# Adafruit_USB_Isolator.net
KiCad netlist of a schematic drawn in EAGLE
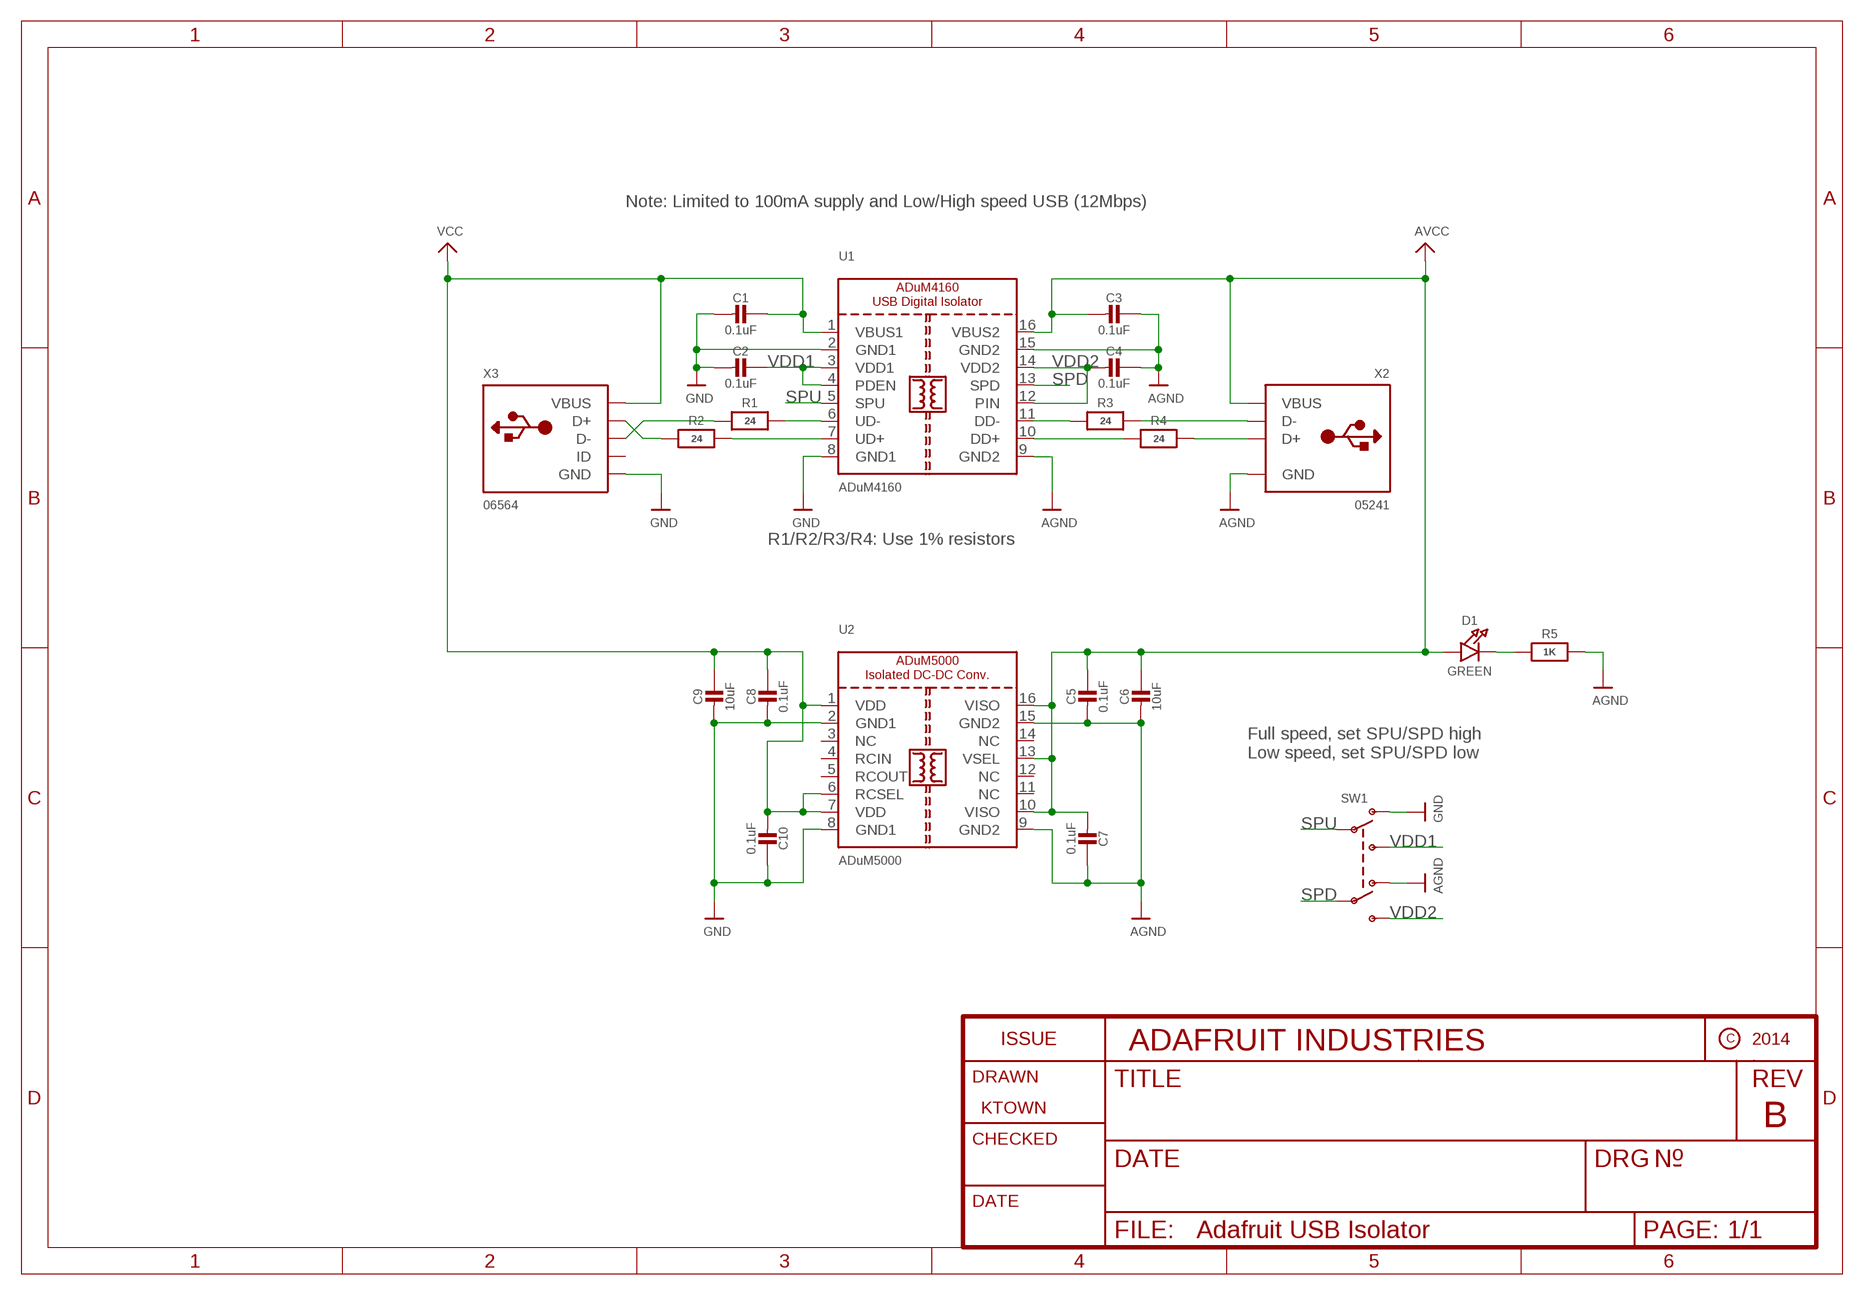
[diagram p0: schematic, sheet 1]

(export (version "E")
  (design (tool "Eeschema 10.0.6"))
  (components
    (comp (ref "C1")
      (value "0.1uF")
      (footprint "eagle-import:0805-NO")
      (libsource (lib "eagle-import") (part "CAP_CERAMIC0805-NOOUTLINE"))
    )
    (comp (ref "C2")
      (value "0.1uF")
      (footprint "eagle-import:0805-NO")
      (libsource (lib "eagle-import") (part "CAP_CERAMIC0805-NOOUTLINE"))
    )
    (comp (ref "C3")
      (value "0.1uF")
      (footprint "eagle-import:0805-NO")
      (libsource (lib "eagle-import") (part "CAP_CERAMIC0805-NOOUTLINE"))
    )
    (comp (ref "C4")
      (value "0.1uF")
      (footprint "eagle-import:0805-NO")
      (libsource (lib "eagle-import") (part "CAP_CERAMIC0805-NOOUTLINE"))
    )
    (comp (ref "C5")
      (value "0.1uF")
      (footprint "eagle-import:0805-NO")
      (libsource (lib "eagle-import") (part "CAP_CERAMIC0805-NOOUTLINE"))
    )
    (comp (ref "C6")
      (value "10uF")
      (footprint "eagle-import:0805-NO")
      (libsource (lib "eagle-import") (part "CAP_CERAMIC0805-NOOUTLINE"))
    )
    (comp (ref "C7")
      (value "0.1uF")
      (footprint "eagle-import:0805-NO")
      (libsource (lib "eagle-import") (part "CAP_CERAMIC0805-NOOUTLINE"))
    )
    (comp (ref "C8")
      (value "0.1uF")
      (footprint "eagle-import:0805-NO")
      (libsource (lib "eagle-import") (part "CAP_CERAMIC0805-NOOUTLINE"))
    )
    (comp (ref "C9")
      (value "10uF")
      (footprint "eagle-import:0805-NO")
      (libsource (lib "eagle-import") (part "CAP_CERAMIC0805-NOOUTLINE"))
    )
    (comp (ref "C10")
      (value "0.1uF")
      (footprint "eagle-import:0805-NO")
      (libsource (lib "eagle-import") (part "CAP_CERAMIC0805-NOOUTLINE"))
    )
    (comp (ref "D1")
      (value "GREEN")
      (footprint "eagle-import:CHIPLED_0805_NOOUTLINE")
      (libsource (lib "eagle-import") (part "LED0805_NOOUTLINE"))
    )
    (comp (ref "R1")
      (value "24")
      (footprint "eagle-import:0805-NO")
      (libsource (lib "eagle-import") (part "RESISTOR0805_NOOUTLINE"))
    )
    (comp (ref "R2")
      (value "24")
      (footprint "eagle-import:0805-NO")
      (libsource (lib "eagle-import") (part "RESISTOR0805_NOOUTLINE"))
    )
    (comp (ref "R3")
      (value "24")
      (footprint "eagle-import:0805-NO")
      (libsource (lib "eagle-import") (part "RESISTOR0805_NOOUTLINE"))
    )
    (comp (ref "R4")
      (value "24")
      (footprint "eagle-import:_0805MP")
      (libsource (lib "eagle-import") (part "RESISTOR_0805MP"))
    )
    (comp (ref "R5")
      (value "1K")
      (footprint "eagle-import:0805-NO")
      (libsource (lib "eagle-import") (part "RESISTOR0805_NOOUTLINE"))
    )
    (comp (ref "SW1")
      (value "SWITCH_DPDTEG1390")
      (footprint "eagle-import:EG1390")
      (libsource (lib "eagle-import") (part "SWITCH_DPDTEG1390"))
    )
    (comp (ref "U1")
      (value "ADuM4160")
      (footprint "eagle-import:SOIC16WIDE")
      (libsource (lib "eagle-import") (part "ADUM4160"))
    )
    (comp (ref "U2")
      (value "ADuM5000")
      (footprint "eagle-import:SOIC16WIDE")
      (libsource (lib "eagle-import") (part "ADUM5000"))
    )
    (comp (ref "X2")
      (value "05241")
      (footprint "eagle-import:USB_HOST-PTH")
      (libsource (lib "eagle-import") (part "USB_TYPEAPTHFML"))
    )
    (comp (ref "X3")
      (value "06564")
      (footprint "eagle-import:USB-MINIB_LARGER")
      (libsource (lib "eagle-import") (part "USBMINIBLARGE"))
    )
  )
  (nets
    (net (code "1") (name "/SPD") (class "Default")
      (node (ref "SW1") (pin "P2") (pinfunction "P2_P2") (pintype "passive"))
      (node (ref "U1") (pin "13") (pinfunction "SPD_13") (pintype "input"))
    )
    (net (code "2") (name "/SPU") (class "Default")
      (node (ref "SW1") (pin "P1") (pinfunction "P1_P1") (pintype "passive"))
      (node (ref "U1") (pin "5") (pinfunction "SPU_5") (pintype "input"))
    )
    (net (code "3") (name "/VDD1") (class "Default")
      (node (ref "C2") (pin "1") (pinfunction "1_1") (pintype "passive"))
      (node (ref "SW1") (pin "S1") (pinfunction "S1_S1") (pintype "passive"))
      (node (ref "U1") (pin "3") (pinfunction "VDD1_3") (pintype "power_in"))
      (node (ref "U1") (pin "4") (pinfunction "PDEN_4") (pintype "input"))
    )
    (net (code "4") (name "/VDD2") (class "Default")
      (node (ref "C4") (pin "2") (pinfunction "2_2") (pintype "passive"))
      (node (ref "SW1") (pin "S2") (pinfunction "S2_S2") (pintype "passive"))
      (node (ref "U1") (pin "12") (pinfunction "PIN_12") (pintype "input"))
      (node (ref "U1") (pin "14") (pinfunction "VDD2_14") (pintype "power_in"))
    )
    (net (code "5") (name "AGND") (class "Default")
      (node (ref "C3") (pin "1") (pinfunction "1_1") (pintype "passive"))
      (node (ref "C4") (pin "1") (pinfunction "1_1") (pintype "passive"))
      (node (ref "C5") (pin "2") (pinfunction "2_2") (pintype "passive"))
      (node (ref "C6") (pin "2") (pinfunction "2_2") (pintype "passive"))
      (node (ref "C7") (pin "1") (pinfunction "1_1") (pintype "passive"))
      (node (ref "R5") (pin "2") (pinfunction "2_2") (pintype "passive"))
      (node (ref "SW1") (pin "O2") (pinfunction "O2_O2") (pintype "passive"))
      (node (ref "U1") (pin "15") (pinfunction "GND2_15") (pintype "power_in"))
      (node (ref "U1") (pin "9") (pinfunction "GND2_9") (pintype "power_in"))
      (node (ref "U2") (pin "15") (pinfunction "GND2_15") (pintype "power_in"))
      (node (ref "U2") (pin "9") (pinfunction "GND2_9") (pintype "power_in"))
      (node (ref "X2") (pin "GND") (pinfunction "GND_GND") (pintype "power_in"))
    )
    (net (code "6") (name "AVCC") (class "Default")
      (node (ref "C3") (pin "2") (pinfunction "2_2") (pintype "passive"))
      (node (ref "C5") (pin "1") (pinfunction "1_1") (pintype "passive"))
      (node (ref "C6") (pin "1") (pinfunction "1_1") (pintype "passive"))
      (node (ref "C7") (pin "2") (pinfunction "2_2") (pintype "passive"))
      (node (ref "D1") (pin "A") (pinfunction "A_A") (pintype "passive"))
      (node (ref "U1") (pin "16") (pinfunction "VBUS2_16") (pintype "power_in"))
      (node (ref "U2") (pin "10") (pinfunction "VISO_10") (pintype "bidirectional"))
      (node (ref "U2") (pin "13") (pinfunction "VSEL_13") (pintype "input"))
      (node (ref "U2") (pin "16") (pinfunction "VISO_16") (pintype "power_in"))
      (node (ref "X2") (pin "VBUS") (pinfunction "VBUS_VBUS") (pintype "power_in"))
    )
    (net (code "7") (name "GND") (class "Default")
      (node (ref "C1") (pin "2") (pinfunction "2_2") (pintype "passive"))
      (node (ref "C10") (pin "1") (pinfunction "1_1") (pintype "passive"))
      (node (ref "C2") (pin "2") (pinfunction "2_2") (pintype "passive"))
      (node (ref "C8") (pin "2") (pinfunction "2_2") (pintype "passive"))
      (node (ref "C9") (pin "2") (pinfunction "2_2") (pintype "passive"))
      (node (ref "SW1") (pin "O1") (pinfunction "O1_O1") (pintype "passive"))
      (node (ref "U1") (pin "2") (pinfunction "GND1_2") (pintype "power_in"))
      (node (ref "U1") (pin "8") (pinfunction "GND1_8") (pintype "power_in"))
      (node (ref "U2") (pin "2") (pinfunction "GND1_2") (pintype "power_in"))
      (node (ref "U2") (pin "8") (pinfunction "GND1_8") (pintype "power_in"))
      (node (ref "X3") (pin "GND") (pinfunction "GND_GND") (pintype "power_in"))
      (node (ref "X3") (pin "GND1") (pinfunction "GND_GND1") (pintype "power_in"))
      (node (ref "X3") (pin "GND2") (pinfunction "GND_GND2") (pintype "power_in"))
      (node (ref "X3") (pin "GND3") (pinfunction "GND_GND3") (pintype "power_in"))
      (node (ref "X3") (pin "GND4") (pinfunction "GND_GND4") (pintype "power_in"))
    )
    (net (code "8") (name "Net-(D1-PadC)") (class "Default")
      (node (ref "D1") (pin "C") (pinfunction "C_C") (pintype "passive"))
      (node (ref "R5") (pin "1") (pinfunction "1_1") (pintype "passive"))
    )
    (net (code "9") (name "Net-(R1-Pad1)") (class "Default")
      (node (ref "R1") (pin "1") (pinfunction "1_1") (pintype "passive"))
      (node (ref "X3") (pin "D-") (pinfunction "D-_D-") (pintype "bidirectional"))
    )
    (net (code "10") (name "Net-(R2-Pad1)") (class "Default")
      (node (ref "R2") (pin "1") (pinfunction "1_1") (pintype "passive"))
      (node (ref "X3") (pin "D+") (pinfunction "D+_D+") (pintype "bidirectional"))
    )
    (net (code "11") (name "Net-(R3-Pad2)") (class "Default")
      (node (ref "R3") (pin "2") (pinfunction "2_2") (pintype "passive"))
      (node (ref "X2") (pin "D-") (pinfunction "D-_D-") (pintype "bidirectional"))
    )
    (net (code "12") (name "Net-(R4-Pad2)") (class "Default")
      (node (ref "R4") (pin "2") (pinfunction "2_2") (pintype "passive"))
      (node (ref "X2") (pin "D+") (pinfunction "D+_D+") (pintype "bidirectional"))
    )
    (net (code "13") (name "Net-(U1-DD+)") (class "Default")
      (node (ref "R4") (pin "1") (pinfunction "1_1") (pintype "passive"))
      (node (ref "U1") (pin "10") (pinfunction "DD+_10") (pintype "bidirectional"))
    )
    (net (code "14") (name "Net-(U1-DD-)") (class "Default")
      (node (ref "R3") (pin "1") (pinfunction "1_1") (pintype "passive"))
      (node (ref "U1") (pin "11") (pinfunction "DD-_11") (pintype "bidirectional"))
    )
    (net (code "15") (name "Net-(U1-UD+)") (class "Default")
      (node (ref "R2") (pin "2") (pinfunction "2_2") (pintype "passive"))
      (node (ref "U1") (pin "7") (pinfunction "UD+_7") (pintype "bidirectional"))
    )
    (net (code "16") (name "Net-(U1-UD-)") (class "Default")
      (node (ref "R1") (pin "2") (pinfunction "2_2") (pintype "passive"))
      (node (ref "U1") (pin "6") (pinfunction "UD-_6") (pintype "bidirectional"))
    )
    (net (code "17") (name "VCC") (class "Default")
      (node (ref "C1") (pin "1") (pinfunction "1_1") (pintype "passive"))
      (node (ref "C10") (pin "2") (pinfunction "2_2") (pintype "passive"))
      (node (ref "C8") (pin "1") (pinfunction "1_1") (pintype "passive"))
      (node (ref "C9") (pin "1") (pinfunction "1_1") (pintype "passive"))
      (node (ref "U1") (pin "1") (pinfunction "VBUS1_1") (pintype "power_in"))
      (node (ref "U2") (pin "1") (pinfunction "VDD_1") (pintype "power_in"))
      (node (ref "U2") (pin "6") (pinfunction "RCSEL_6") (pintype "input"))
      (node (ref "U2") (pin "7") (pinfunction "VDD_7") (pintype "bidirectional"))
      (node (ref "X3") (pin "VBUS") (pinfunction "VBUS_VBUS") (pintype "power_in"))
    )
    (net (code "18") (name "unconnected-(U2-NC-Pad3)") (class "Default")
      (node (ref "U2") (pin "3") (pinfunction "NC_3") (pintype "no_connect"))
    )
    (net (code "19") (name "unconnected-(U2-NC-Pad11)") (class "Default")
      (node (ref "U2") (pin "11") (pinfunction "NC_11") (pintype "no_connect"))
    )
    (net (code "20") (name "unconnected-(U2-NC-Pad12)") (class "Default")
      (node (ref "U2") (pin "12") (pinfunction "NC_12") (pintype "no_connect"))
    )
    (net (code "21") (name "unconnected-(U2-NC-Pad14)") (class "Default")
      (node (ref "U2") (pin "14") (pinfunction "NC_14") (pintype "no_connect"))
    )
    (net (code "22") (name "unconnected-(U2-RCIN-Pad4)") (class "Default")
      (node (ref "U2") (pin "4") (pinfunction "RCIN_4") (pintype "input"))
    )
    (net (code "23") (name "unconnected-(U2-RCOUT-Pad5)") (class "Default")
      (node (ref "U2") (pin "5") (pinfunction "RCOUT_5") (pintype "output"))
    )
    (net (code "24") (name "unconnected-(X3-PadID)") (class "Default")
      (node (ref "X3") (pin "ID") (pinfunction "ID_ID") (pintype "bidirectional"))
    )
  )
)
